# m80-v0_60.net
KiCad netlist of a schematic drawn in EAGLE
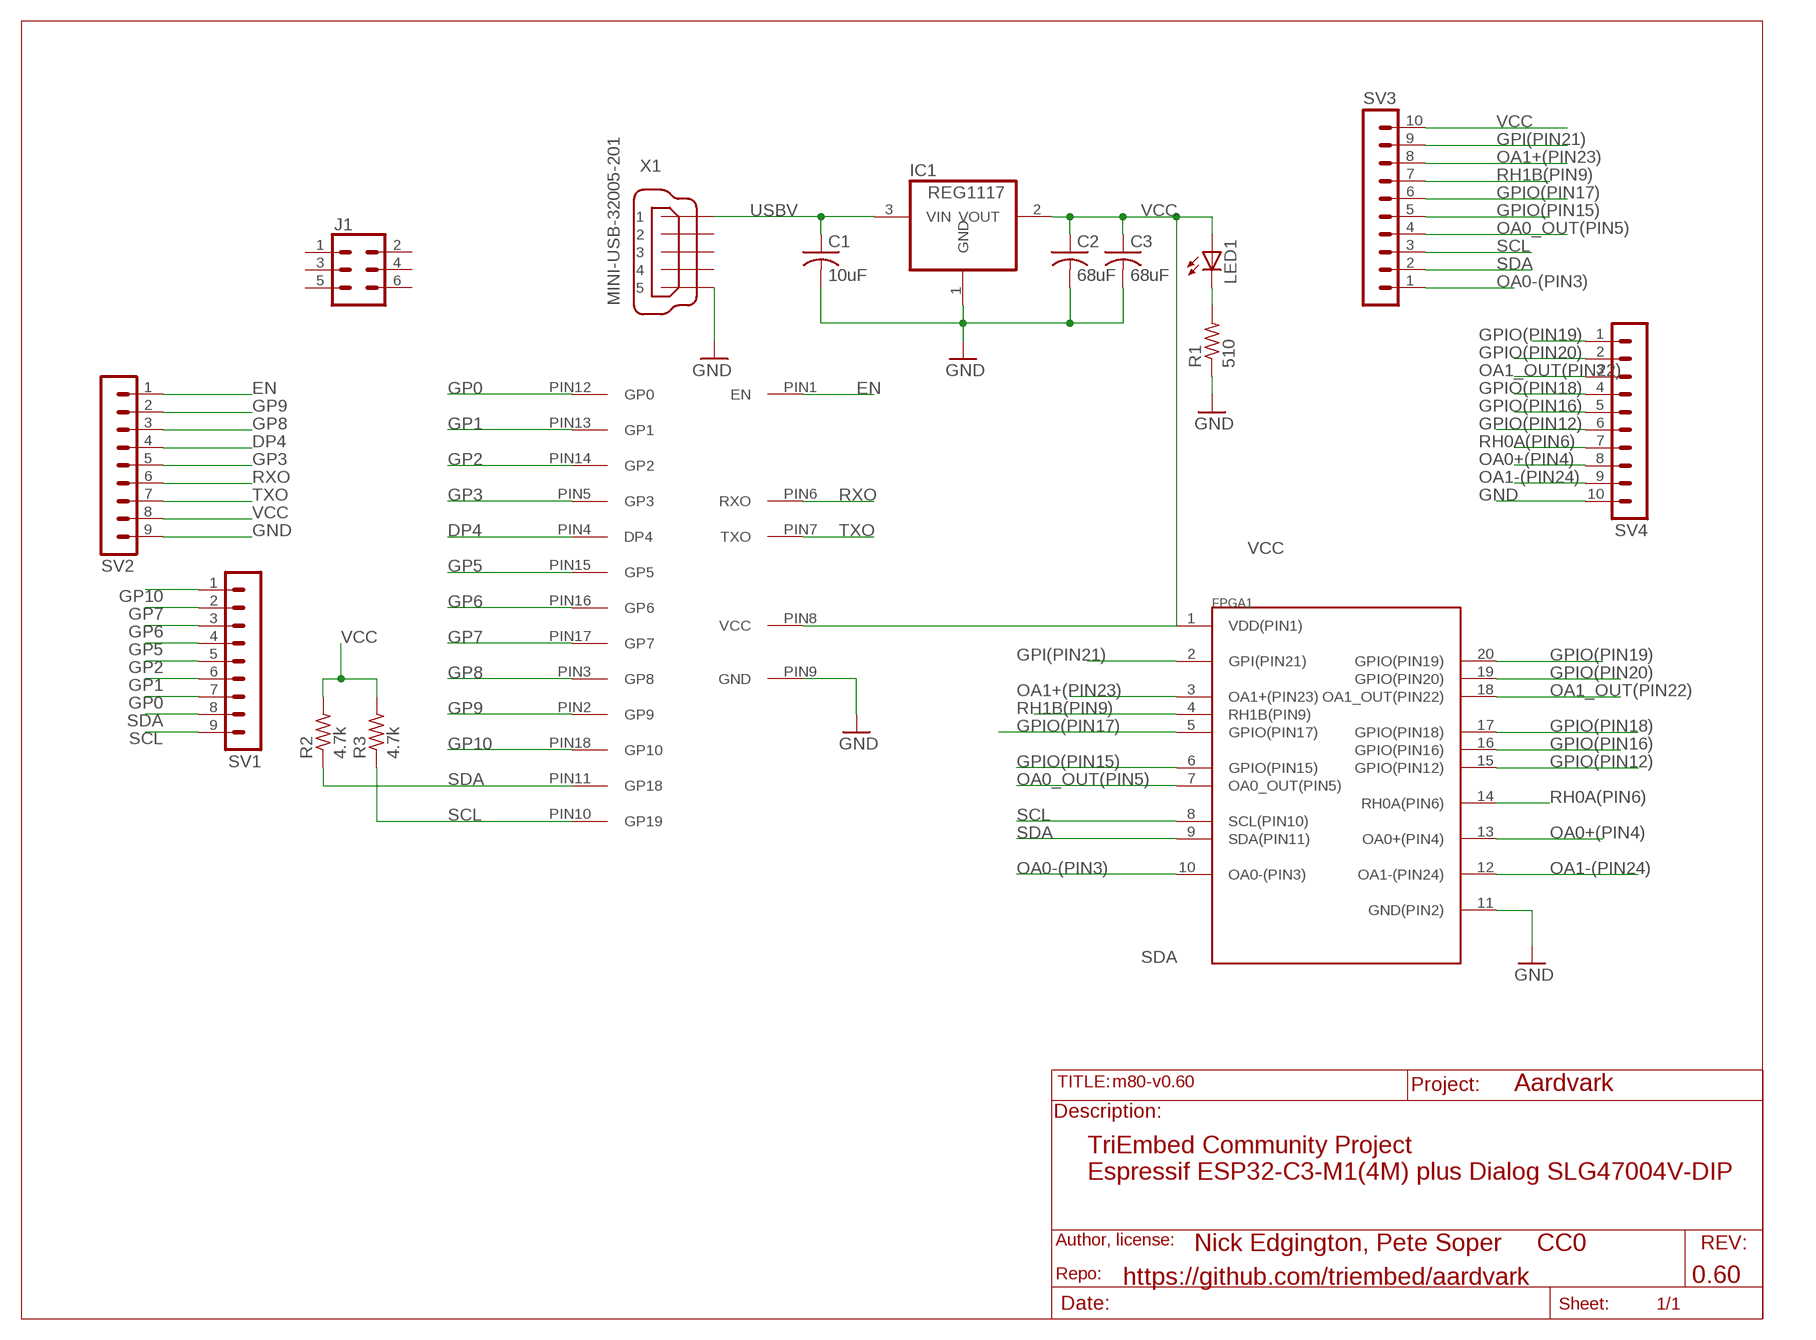
[diagram p0: schematic, sheet 1]

(export (version "E")
  (design (tool "Eeschema 10.0.6"))
  (components
    (comp (ref "C1")
      (value "10uF")
      (footprint "eagle-import:C0805")
      (libsource (lib "eagle-import") (part "C-USC0805"))
    )
    (comp (ref "C2")
      (value "68uF")
      (footprint "eagle-import:C1206")
      (libsource (lib "eagle-import") (part "C-USC1206"))
    )
    (comp (ref "C3")
      (value "68uF")
      (footprint "eagle-import:C1206")
      (libsource (lib "eagle-import") (part "C-USC1206"))
    )
    (comp (ref "FPGA1")
      (value "SLG7004V_DIP")
      (footprint "eagle-import:SLG47004V-DIP")
      (libsource (lib "eagle-import") (part "SLG7004V_DIP"))
    )
    (comp (ref "IC1")
      (value "REG1117")
      (footprint "eagle-import:SOT223")
      (libsource (lib "eagle-import") (part "REG1117"))
    )
    (comp (ref "J1")
      (value "CONN_03X2NO_SILK")
      (footprint "eagle-import:2X3-NS")
      (libsource (lib "eagle-import") (part "CONN_03X2NO_SILK"))
    )
    (comp (ref "LED1")
      (value "LEDCHIP-LED0805")
      (footprint "eagle-import:CHIP-LED0805")
      (libsource (lib "eagle-import") (part "LEDCHIP-LED0805"))
    )
    (comp (ref "R1")
      (value "510")
      (footprint "eagle-import:R0805")
      (libsource (lib "eagle-import") (part "R-US_R0805"))
    )
    (comp (ref "R2")
      (value "4.7k")
      (footprint "eagle-import:R0805")
      (libsource (lib "eagle-import") (part "R-US_R0805"))
    )
    (comp (ref "R3")
      (value "4.7k")
      (footprint "eagle-import:R0805")
      (libsource (lib "eagle-import") (part "R-US_R0805"))
    )
    (comp (ref "SV1")
      (value "MA09-1")
      (footprint "eagle-import:MA09-1")
      (libsource (lib "eagle-import") (part "MA09-1"))
    )
    (comp (ref "SV2")
      (value "MA09-1")
      (footprint "eagle-import:MA09-1")
      (libsource (lib "eagle-import") (part "MA09-1"))
    )
    (comp (ref "SV3")
      (value "MA10-1")
      (footprint "eagle-import:MA10-1")
      (libsource (lib "eagle-import") (part "MA10-1"))
    )
    (comp (ref "SV4")
      (value "MA10-1")
      (footprint "eagle-import:MA10-1")
      (libsource (lib "eagle-import") (part "MA10-1"))
    )
    (comp (ref "U$2")
      (value "UNTITLED_ESP32C3")
      (footprint "eagle-import:UNTITLED_ESP32-C3-01M")
      (libsource (lib "eagle-import") (part "UNTITLED_ESP32C3"))
    )
    (comp (ref "X1")
      (value "MINI-USB-32005-201")
      (footprint "eagle-import:32005-201")
      (libsource (lib "eagle-import") (part "MINI-USB-32005-201"))
    )
  )
  (nets
    (net (code "1") (name "/DP4") (class "Default")
      (node (ref "SV2") (pin "4") (pinfunction "4_4") (pintype "passive"))
      (node (ref "U$2") (pin "PIN4") (pinfunction "DP4_PIN4") (pintype "bidirectional"))
    )
    (net (code "2") (name "/EN") (class "Default")
      (node (ref "SV2") (pin "1") (pinfunction "1_1") (pintype "passive"))
      (node (ref "U$2") (pin "PIN1") (pinfunction "EN_PIN1") (pintype "input"))
    )
    (net (code "3") (name "/GP0") (class "Default")
      (node (ref "SV1") (pin "7") (pinfunction "7_7") (pintype "passive"))
      (node (ref "U$2") (pin "PIN12") (pinfunction "GP0_PIN12") (pintype "bidirectional"))
    )
    (net (code "4") (name "/GP1") (class "Default")
      (node (ref "SV1") (pin "6") (pinfunction "6_6") (pintype "passive"))
      (node (ref "U$2") (pin "PIN13") (pinfunction "GP1_PIN13") (pintype "bidirectional"))
    )
    (net (code "5") (name "/GP2") (class "Default")
      (node (ref "SV1") (pin "5") (pinfunction "5_5") (pintype "passive"))
      (node (ref "U$2") (pin "PIN14") (pinfunction "GP2_PIN14") (pintype "bidirectional"))
    )
    (net (code "6") (name "/GP3") (class "Default")
      (node (ref "SV2") (pin "5") (pinfunction "5_5") (pintype "passive"))
      (node (ref "U$2") (pin "PIN5") (pinfunction "GP3_PIN5") (pintype "bidirectional"))
    )
    (net (code "7") (name "/GP5") (class "Default")
      (node (ref "SV1") (pin "4") (pinfunction "4_4") (pintype "passive"))
      (node (ref "U$2") (pin "PIN15") (pinfunction "GP5_PIN15") (pintype "bidirectional"))
    )
    (net (code "8") (name "/GP6") (class "Default")
      (node (ref "SV1") (pin "3") (pinfunction "3_3") (pintype "passive"))
      (node (ref "U$2") (pin "PIN16") (pinfunction "GP6_PIN16") (pintype "bidirectional"))
    )
    (net (code "9") (name "/GP7") (class "Default")
      (node (ref "SV1") (pin "2") (pinfunction "2_2") (pintype "passive"))
      (node (ref "U$2") (pin "PIN17") (pinfunction "GP7_PIN17") (pintype "bidirectional"))
    )
    (net (code "10") (name "/GP8") (class "Default")
      (node (ref "SV2") (pin "3") (pinfunction "3_3") (pintype "passive"))
      (node (ref "U$2") (pin "PIN3") (pinfunction "GP8_PIN3") (pintype "bidirectional"))
    )
    (net (code "11") (name "/GP9") (class "Default")
      (node (ref "SV2") (pin "2") (pinfunction "2_2") (pintype "passive"))
      (node (ref "U$2") (pin "PIN2") (pinfunction "GP9_PIN2") (pintype "bidirectional"))
    )
    (net (code "12") (name "/GP10") (class "Default")
      (node (ref "SV1") (pin "1") (pinfunction "1_1") (pintype "passive"))
      (node (ref "U$2") (pin "PIN18") (pinfunction "GP10_PIN18") (pintype "bidirectional"))
    )
    (net (code "13") (name "/GPI(PIN21)") (class "Default")
      (node (ref "FPGA1") (pin "2") (pinfunction "GPI(PIN21)_2") (pintype "input"))
      (node (ref "SV3") (pin "9") (pinfunction "9_9") (pintype "passive"))
    )
    (net (code "14") (name "/GPIO(PIN12)") (class "Default")
      (node (ref "FPGA1") (pin "15") (pinfunction "GPIO(PIN12)_15") (pintype "bidirectional"))
      (node (ref "SV4") (pin "6") (pinfunction "6_6") (pintype "passive"))
    )
    (net (code "15") (name "/GPIO(PIN15)") (class "Default")
      (node (ref "FPGA1") (pin "6") (pinfunction "GPIO(PIN15)_6") (pintype "bidirectional"))
      (node (ref "SV3") (pin "5") (pinfunction "5_5") (pintype "passive"))
    )
    (net (code "16") (name "/GPIO(PIN16)") (class "Default")
      (node (ref "FPGA1") (pin "16") (pinfunction "GPIO(PIN16)_16") (pintype "bidirectional"))
      (node (ref "SV4") (pin "5") (pinfunction "5_5") (pintype "passive"))
    )
    (net (code "17") (name "/GPIO(PIN17)") (class "Default")
      (node (ref "FPGA1") (pin "5") (pinfunction "GPIO(PIN17)_5") (pintype "bidirectional"))
      (node (ref "SV3") (pin "6") (pinfunction "6_6") (pintype "passive"))
    )
    (net (code "18") (name "/GPIO(PIN18)") (class "Default")
      (node (ref "FPGA1") (pin "17") (pinfunction "GPIO(PIN18)_17") (pintype "input"))
      (node (ref "SV4") (pin "4") (pinfunction "4_4") (pintype "passive"))
    )
    (net (code "19") (name "/GPIO(PIN19)") (class "Default")
      (node (ref "FPGA1") (pin "20") (pinfunction "GPIO(PIN19)_20") (pintype "bidirectional"))
      (node (ref "SV4") (pin "1") (pinfunction "1_1") (pintype "passive"))
    )
    (net (code "20") (name "/GPIO(PIN20)") (class "Default")
      (node (ref "FPGA1") (pin "19") (pinfunction "GPIO(PIN20)_19") (pintype "bidirectional"))
      (node (ref "SV4") (pin "2") (pinfunction "2_2") (pintype "passive"))
    )
    (net (code "21") (name "/OA0+(PIN4)") (class "Default")
      (node (ref "FPGA1") (pin "13") (pinfunction "OA0+(PIN4)_13") (pintype "bidirectional"))
      (node (ref "SV4") (pin "8") (pinfunction "8_8") (pintype "passive"))
    )
    (net (code "22") (name "/OA0-(PIN3)") (class "Default")
      (node (ref "FPGA1") (pin "10") (pinfunction "OA0-(PIN3)_10") (pintype "open_collector"))
      (node (ref "SV3") (pin "1") (pinfunction "1_1") (pintype "passive"))
    )
    (net (code "23") (name "/OA0_OUT(PIN5)") (class "Default")
      (node (ref "FPGA1") (pin "7") (pinfunction "OA0_OUT(PIN5)_7") (pintype "bidirectional"))
      (node (ref "SV3") (pin "4") (pinfunction "4_4") (pintype "passive"))
    )
    (net (code "24") (name "/OA1+(PIN23)") (class "Default")
      (node (ref "FPGA1") (pin "3") (pinfunction "OA1+(PIN23)_3") (pintype "bidirectional"))
      (node (ref "SV3") (pin "8") (pinfunction "8_8") (pintype "passive"))
    )
    (net (code "25") (name "/OA1-(PIN24)") (class "Default")
      (node (ref "FPGA1") (pin "12") (pinfunction "OA1-(PIN24)_12") (pintype "bidirectional"))
      (node (ref "SV4") (pin "9") (pinfunction "9_9") (pintype "passive"))
    )
    (net (code "26") (name "/OA1_OUT(PIN22)") (class "Default")
      (node (ref "FPGA1") (pin "18") (pinfunction "OA1_OUT(PIN22)_18") (pintype "bidirectional"))
      (node (ref "SV4") (pin "3") (pinfunction "3_3") (pintype "passive"))
    )
    (net (code "27") (name "/RH0A(PIN6)") (class "Default")
      (node (ref "FPGA1") (pin "14") (pinfunction "RH0A(PIN6)_14") (pintype "passive"))
      (node (ref "SV4") (pin "7") (pinfunction "7_7") (pintype "passive"))
    )
    (net (code "28") (name "/RH1B(PIN9)") (class "Default")
      (node (ref "FPGA1") (pin "4") (pinfunction "RH1B(PIN9)_4") (pintype "passive"))
      (node (ref "SV3") (pin "7") (pinfunction "7_7") (pintype "passive"))
    )
    (net (code "29") (name "/RXO") (class "Default")
      (node (ref "SV2") (pin "6") (pinfunction "6_6") (pintype "passive"))
      (node (ref "U$2") (pin "PIN6") (pinfunction "RXO_PIN6") (pintype "bidirectional"))
    )
    (net (code "30") (name "/SCL") (class "Default")
      (node (ref "FPGA1") (pin "8") (pinfunction "SCL(PIN10)_8") (pintype "bidirectional"))
      (node (ref "R3") (pin "1") (pinfunction "1_1") (pintype "passive"))
      (node (ref "SV1") (pin "9") (pinfunction "9_9") (pintype "passive"))
      (node (ref "SV3") (pin "3") (pinfunction "3_3") (pintype "passive"))
      (node (ref "U$2") (pin "PIN10") (pinfunction "GP19_PIN10") (pintype "bidirectional"))
    )
    (net (code "31") (name "/SDA") (class "Default")
      (node (ref "FPGA1") (pin "9") (pinfunction "SDA(PIN11)_9") (pintype "bidirectional"))
      (node (ref "R2") (pin "1") (pinfunction "1_1") (pintype "passive"))
      (node (ref "SV1") (pin "8") (pinfunction "8_8") (pintype "passive"))
      (node (ref "SV3") (pin "2") (pinfunction "2_2") (pintype "passive"))
      (node (ref "U$2") (pin "PIN11") (pinfunction "GP18_PIN11") (pintype "bidirectional"))
    )
    (net (code "32") (name "/TXO") (class "Default")
      (node (ref "SV2") (pin "7") (pinfunction "7_7") (pintype "passive"))
      (node (ref "U$2") (pin "PIN7") (pinfunction "TXO_PIN7") (pintype "bidirectional"))
    )
    (net (code "33") (name "/USBV") (class "Default")
      (node (ref "C1") (pin "1") (pinfunction "1_1") (pintype "passive"))
      (node (ref "IC1") (pin "3") (pinfunction "VIN_3") (pintype "input"))
      (node (ref "X1") (pin "1") (pinfunction "1_1") (pintype "passive"))
    )
    (net (code "34") (name "/VCC") (class "Default")
      (node (ref "C2") (pin "1") (pinfunction "1_1") (pintype "passive"))
      (node (ref "C3") (pin "1") (pinfunction "1_1") (pintype "passive"))
      (node (ref "FPGA1") (pin "1") (pinfunction "VDD(PIN1)_1") (pintype "power_in"))
      (node (ref "IC1") (pin "2") (pinfunction "VOUT_2") (pintype "output"))
      (node (ref "LED1") (pin "A") (pinfunction "A_A") (pintype "passive"))
      (node (ref "R2") (pin "2") (pinfunction "2_2") (pintype "passive"))
      (node (ref "R3") (pin "2") (pinfunction "2_2") (pintype "passive"))
      (node (ref "SV2") (pin "8") (pinfunction "8_8") (pintype "passive"))
      (node (ref "SV3") (pin "10") (pinfunction "10_10") (pintype "passive"))
      (node (ref "U$2") (pin "PIN8") (pinfunction "VCC_PIN8") (pintype "power_in"))
    )
    (net (code "35") (name "GND") (class "Default")
      (node (ref "C1") (pin "2") (pinfunction "2_2") (pintype "passive"))
      (node (ref "C2") (pin "2") (pinfunction "2_2") (pintype "passive"))
      (node (ref "C3") (pin "2") (pinfunction "2_2") (pintype "passive"))
      (node (ref "FPGA1") (pin "11") (pinfunction "GND(PIN2)_11") (pintype "power_in"))
      (node (ref "IC1") (pin "1") (pinfunction "GND_1") (pintype "power_in"))
      (node (ref "R1") (pin "1") (pinfunction "1_1") (pintype "passive"))
      (node (ref "SV2") (pin "9") (pinfunction "9_9") (pintype "passive"))
      (node (ref "SV4") (pin "10") (pinfunction "10_10") (pintype "passive"))
      (node (ref "U$2") (pin "PIN9") (pinfunction "GND_PIN9") (pintype "power_in"))
      (node (ref "X1") (pin "5") (pinfunction "5_5") (pintype "passive"))
    )
    (net (code "36") (name "Net-(LED1-PadC)") (class "Default")
      (node (ref "LED1") (pin "C") (pinfunction "C_C") (pintype "passive"))
      (node (ref "R1") (pin "2") (pinfunction "2_2") (pintype "passive"))
    )
    (net (code "37") (name "unconnected-(J1-Pad1)") (class "Default")
      (node (ref "J1") (pin "1") (pinfunction "1_1") (pintype "bidirectional"))
    )
    (net (code "38") (name "unconnected-(J1-Pad2)") (class "Default")
      (node (ref "J1") (pin "2") (pinfunction "2_2") (pintype "bidirectional"))
    )
    (net (code "39") (name "unconnected-(J1-Pad3)") (class "Default")
      (node (ref "J1") (pin "3") (pinfunction "3_3") (pintype "bidirectional"))
    )
    (net (code "40") (name "unconnected-(J1-Pad4)") (class "Default")
      (node (ref "J1") (pin "4") (pinfunction "4_4") (pintype "bidirectional"))
    )
    (net (code "41") (name "unconnected-(J1-Pad5)") (class "Default")
      (node (ref "J1") (pin "5") (pinfunction "5_5") (pintype "bidirectional"))
    )
    (net (code "42") (name "unconnected-(J1-Pad6)") (class "Default")
      (node (ref "J1") (pin "6") (pinfunction "6_6") (pintype "bidirectional"))
    )
    (net (code "43") (name "unconnected-(X1-Pad2)") (class "Default")
      (node (ref "X1") (pin "2") (pinfunction "2_2") (pintype "passive"))
    )
    (net (code "44") (name "unconnected-(X1-Pad3)") (class "Default")
      (node (ref "X1") (pin "3") (pinfunction "3_3") (pintype "passive"))
    )
    (net (code "45") (name "unconnected-(X1-Pad4)") (class "Default")
      (node (ref "X1") (pin "4") (pinfunction "4_4") (pintype "passive"))
    )
  )
)
